# finalizeScale.net
KiCad netlist of a schematic drawn in EAGLE
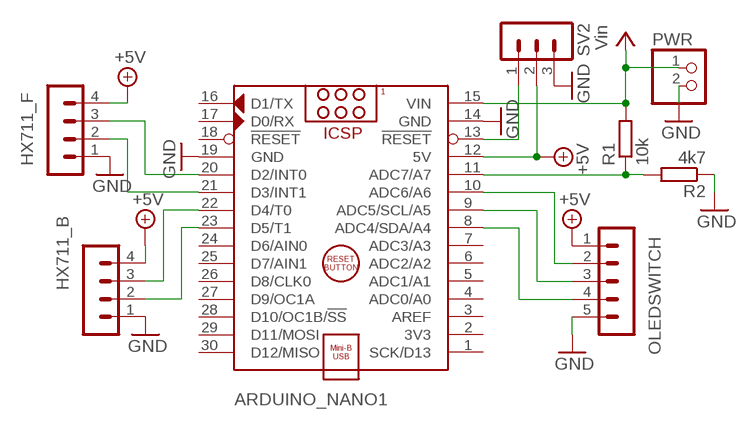
[diagram p0: schematic, sheet 1]

(export (version "E")
  (design (tool "Eeschema 10.0.6"))
  (components
    (comp (ref "ARDUINO_NANO1")
      (value "ARDUINO_NANO")
      (footprint "eagle-import:ARDUINO_NANO")
      (libsource (lib "eagle-import") (part "ARDUINO_NANO"))
    )
    (comp (ref "HX711_B")
      (value "MA04-1")
      (footprint "eagle-import:MA04-1")
      (libsource (lib "eagle-import") (part "MA04-1"))
    )
    (comp (ref "HX711_F")
      (value "MA04-1")
      (footprint "eagle-import:MA04-1")
      (libsource (lib "eagle-import") (part "MA04-1"))
    )
    (comp (ref "OLEDSWITCH")
      (value "MA05-1")
      (footprint "eagle-import:MA05-1")
      (libsource (lib "eagle-import") (part "MA05-1"))
    )
    (comp (ref "PWR")
      (value "PINHD-1X2")
      (footprint "eagle-import:1X02")
      (libsource (lib "eagle-import") (part "PINHD-1X2"))
    )
    (comp (ref "R1")
      (value "10k")
      (footprint "eagle-import:0207_10")
      (libsource (lib "eagle-import") (part "R-EU_0207/10"))
    )
    (comp (ref "R2")
      (value "4k7")
      (footprint "eagle-import:0207_10")
      (libsource (lib "eagle-import") (part "R-EU_0207/10"))
    )
    (comp (ref "SV2")
      (value "MA03-1")
      (footprint "eagle-import:MA03-1")
      (libsource (lib "eagle-import") (part "MA03-1"))
    )
  )
  (nets
    (net (code "1") (name "+5V") (class "Default")
      (node (ref "ARDUINO_NANO1") (pin "12") (pinfunction "5V_12") (pintype "power_in"))
      (node (ref "HX711_B") (pin "4") (pinfunction "4_4") (pintype "passive"))
      (node (ref "HX711_F") (pin "4") (pinfunction "4_4") (pintype "passive"))
      (node (ref "OLEDSWITCH") (pin "1") (pinfunction "1_1") (pintype "passive"))
      (node (ref "SV2") (pin "2") (pinfunction "2_2") (pintype "passive"))
    )
    (net (code "2") (name "GND") (class "Default")
      (node (ref "ARDUINO_NANO1") (pin "14") (pinfunction "GND_14") (pintype "power_in"))
      (node (ref "ARDUINO_NANO1") (pin "19") (pinfunction "GND_19") (pintype "power_in"))
      (node (ref "HX711_B") (pin "1") (pinfunction "1_1") (pintype "passive"))
      (node (ref "HX711_F") (pin "1") (pinfunction "1_1") (pintype "passive"))
      (node (ref "OLEDSWITCH") (pin "5") (pinfunction "5_5") (pintype "passive"))
      (node (ref "PWR") (pin "2") (pinfunction "2_2") (pintype "passive"))
      (node (ref "R2") (pin "1") (pinfunction "1_1") (pintype "passive"))
      (node (ref "SV2") (pin "3") (pinfunction "3_3") (pintype "passive"))
    )
    (net (code "3") (name "Net-(ARDUINO_NANO1-ADC4{slash}SDA{slash}A4)") (class "Default")
      (node (ref "ARDUINO_NANO1") (pin "8") (pinfunction "ADC4/SDA/A4_8") (pintype "bidirectional"))
      (node (ref "OLEDSWITCH") (pin "4") (pinfunction "4_4") (pintype "passive"))
    )
    (net (code "4") (name "Net-(ARDUINO_NANO1-ADC5{slash}SCL{slash}A5)") (class "Default")
      (node (ref "ARDUINO_NANO1") (pin "9") (pinfunction "ADC5/SCL/A5_9") (pintype "bidirectional"))
      (node (ref "OLEDSWITCH") (pin "3") (pinfunction "3_3") (pintype "passive"))
    )
    (net (code "5") (name "Net-(ARDUINO_NANO1-ADC6{slash}A6)") (class "Default")
      (node (ref "ARDUINO_NANO1") (pin "10") (pinfunction "ADC6/A6_10") (pintype "bidirectional"))
      (node (ref "OLEDSWITCH") (pin "2") (pinfunction "2_2") (pintype "passive"))
    )
    (net (code "6") (name "Net-(ARDUINO_NANO1-ADC7{slash}A7)") (class "Default")
      (node (ref "ARDUINO_NANO1") (pin "11") (pinfunction "ADC7/A7_11") (pintype "bidirectional"))
      (node (ref "R1") (pin "1") (pinfunction "1_1") (pintype "passive"))
      (node (ref "R2") (pin "2") (pinfunction "2_2") (pintype "passive"))
    )
    (net (code "7") (name "Net-(ARDUINO_NANO1-D2{slash}INT0)") (class "Default")
      (node (ref "ARDUINO_NANO1") (pin "20") (pinfunction "D2/INT0_20") (pintype "bidirectional"))
      (node (ref "HX711_F") (pin "3") (pinfunction "3_3") (pintype "passive"))
    )
    (net (code "8") (name "Net-(ARDUINO_NANO1-D3{slash}INT1)") (class "Default")
      (node (ref "ARDUINO_NANO1") (pin "21") (pinfunction "D3/INT1_21") (pintype "bidirectional"))
      (node (ref "HX711_F") (pin "2") (pinfunction "2_2") (pintype "passive"))
    )
    (net (code "9") (name "Net-(ARDUINO_NANO1-D4{slash}T0)") (class "Default")
      (node (ref "ARDUINO_NANO1") (pin "22") (pinfunction "D4/T0_22") (pintype "bidirectional"))
      (node (ref "HX711_B") (pin "3") (pinfunction "3_3") (pintype "passive"))
    )
    (net (code "10") (name "Net-(ARDUINO_NANO1-D5{slash}T1)") (class "Default")
      (node (ref "ARDUINO_NANO1") (pin "23") (pinfunction "D5/T1_23") (pintype "bidirectional"))
      (node (ref "HX711_B") (pin "2") (pinfunction "2_2") (pintype "passive"))
    )
    (net (code "11") (name "Net-(ARDUINO_NANO1-~{RESET}-Pad13)") (class "Default")
      (node (ref "ARDUINO_NANO1") (pin "13") (pinfunction "~{RESET}_13") (pintype "input"))
      (node (ref "SV2") (pin "1") (pinfunction "1_1") (pintype "passive"))
    )
    (net (code "12") (name "Vin") (class "Default")
      (node (ref "ARDUINO_NANO1") (pin "15") (pinfunction "VIN_15") (pintype "power_in"))
      (node (ref "PWR") (pin "1") (pinfunction "1_1") (pintype "passive"))
      (node (ref "R1") (pin "2") (pinfunction "2_2") (pintype "passive"))
    )
    (net (code "13") (name "unconnected-(ARDUINO_NANO1-3V3-Pad2)") (class "Default")
      (node (ref "ARDUINO_NANO1") (pin "2") (pinfunction "3V3_2") (pintype "output"))
    )
    (net (code "14") (name "unconnected-(ARDUINO_NANO1-ADC0{slash}A0-Pad4)") (class "Default")
      (node (ref "ARDUINO_NANO1") (pin "4") (pinfunction "ADC0/A0_4") (pintype "bidirectional"))
    )
    (net (code "15") (name "unconnected-(ARDUINO_NANO1-ADC1{slash}A1-Pad5)") (class "Default")
      (node (ref "ARDUINO_NANO1") (pin "5") (pinfunction "ADC1/A1_5") (pintype "bidirectional"))
    )
    (net (code "16") (name "unconnected-(ARDUINO_NANO1-ADC2{slash}A2-Pad6)") (class "Default")
      (node (ref "ARDUINO_NANO1") (pin "6") (pinfunction "ADC2/A2_6") (pintype "bidirectional"))
    )
    (net (code "17") (name "unconnected-(ARDUINO_NANO1-ADC3{slash}A3-Pad7)") (class "Default")
      (node (ref "ARDUINO_NANO1") (pin "7") (pinfunction "ADC3/A3_7") (pintype "bidirectional"))
    )
    (net (code "18") (name "unconnected-(ARDUINO_NANO1-AREF-Pad3)") (class "Default")
      (node (ref "ARDUINO_NANO1") (pin "3") (pinfunction "AREF_3") (pintype "input"))
    )
    (net (code "19") (name "unconnected-(ARDUINO_NANO1-D0{slash}RX-Pad17)") (class "Default")
      (node (ref "ARDUINO_NANO1") (pin "17") (pinfunction "D0/RX_17") (pintype "bidirectional"))
    )
    (net (code "20") (name "unconnected-(ARDUINO_NANO1-D1{slash}TX-Pad16)") (class "Default")
      (node (ref "ARDUINO_NANO1") (pin "16") (pinfunction "D1/TX_16") (pintype "bidirectional"))
    )
    (net (code "21") (name "unconnected-(ARDUINO_NANO1-D6{slash}AIN0-Pad24)") (class "Default")
      (node (ref "ARDUINO_NANO1") (pin "24") (pinfunction "D6/AIN0_24") (pintype "bidirectional"))
    )
    (net (code "22") (name "unconnected-(ARDUINO_NANO1-D7{slash}AIN1-Pad25)") (class "Default")
      (node (ref "ARDUINO_NANO1") (pin "25") (pinfunction "D7/AIN1_25") (pintype "bidirectional"))
    )
    (net (code "23") (name "unconnected-(ARDUINO_NANO1-D8{slash}CLK0-Pad26)") (class "Default")
      (node (ref "ARDUINO_NANO1") (pin "26") (pinfunction "D8/CLK0_26") (pintype "bidirectional"))
    )
    (net (code "24") (name "unconnected-(ARDUINO_NANO1-D9{slash}OC1A-Pad27)") (class "Default")
      (node (ref "ARDUINO_NANO1") (pin "27") (pinfunction "D9/OC1A_27") (pintype "bidirectional"))
    )
    (net (code "25") (name "unconnected-(ARDUINO_NANO1-D10{slash}OC1B{slash}~{SS}-Pad28)") (class "Default")
      (node (ref "ARDUINO_NANO1") (pin "28") (pinfunction "D10/OC1B/~{SS}_28") (pintype "bidirectional"))
    )
    (net (code "26") (name "unconnected-(ARDUINO_NANO1-D11{slash}MOSI-Pad29)") (class "Default")
      (node (ref "ARDUINO_NANO1") (pin "29") (pinfunction "D11/MOSI_29") (pintype "bidirectional"))
    )
    (net (code "27") (name "unconnected-(ARDUINO_NANO1-D12{slash}MISO-Pad30)") (class "Default")
      (node (ref "ARDUINO_NANO1") (pin "30") (pinfunction "D12/MISO_30") (pintype "bidirectional"))
    )
    (net (code "28") (name "unconnected-(ARDUINO_NANO1-SCK{slash}D13-Pad1)") (class "Default")
      (node (ref "ARDUINO_NANO1") (pin "1") (pinfunction "SCK/D13_1") (pintype "bidirectional"))
    )
    (net (code "29") (name "unconnected-(ARDUINO_NANO1-~{RESET}-Pad18)") (class "Default")
      (node (ref "ARDUINO_NANO1") (pin "18") (pinfunction "~{RESET}_18") (pintype "input"))
    )
  )
)
